# MotorController-ControlCard.net
KiCad netlist of a schematic drawn in EAGLE
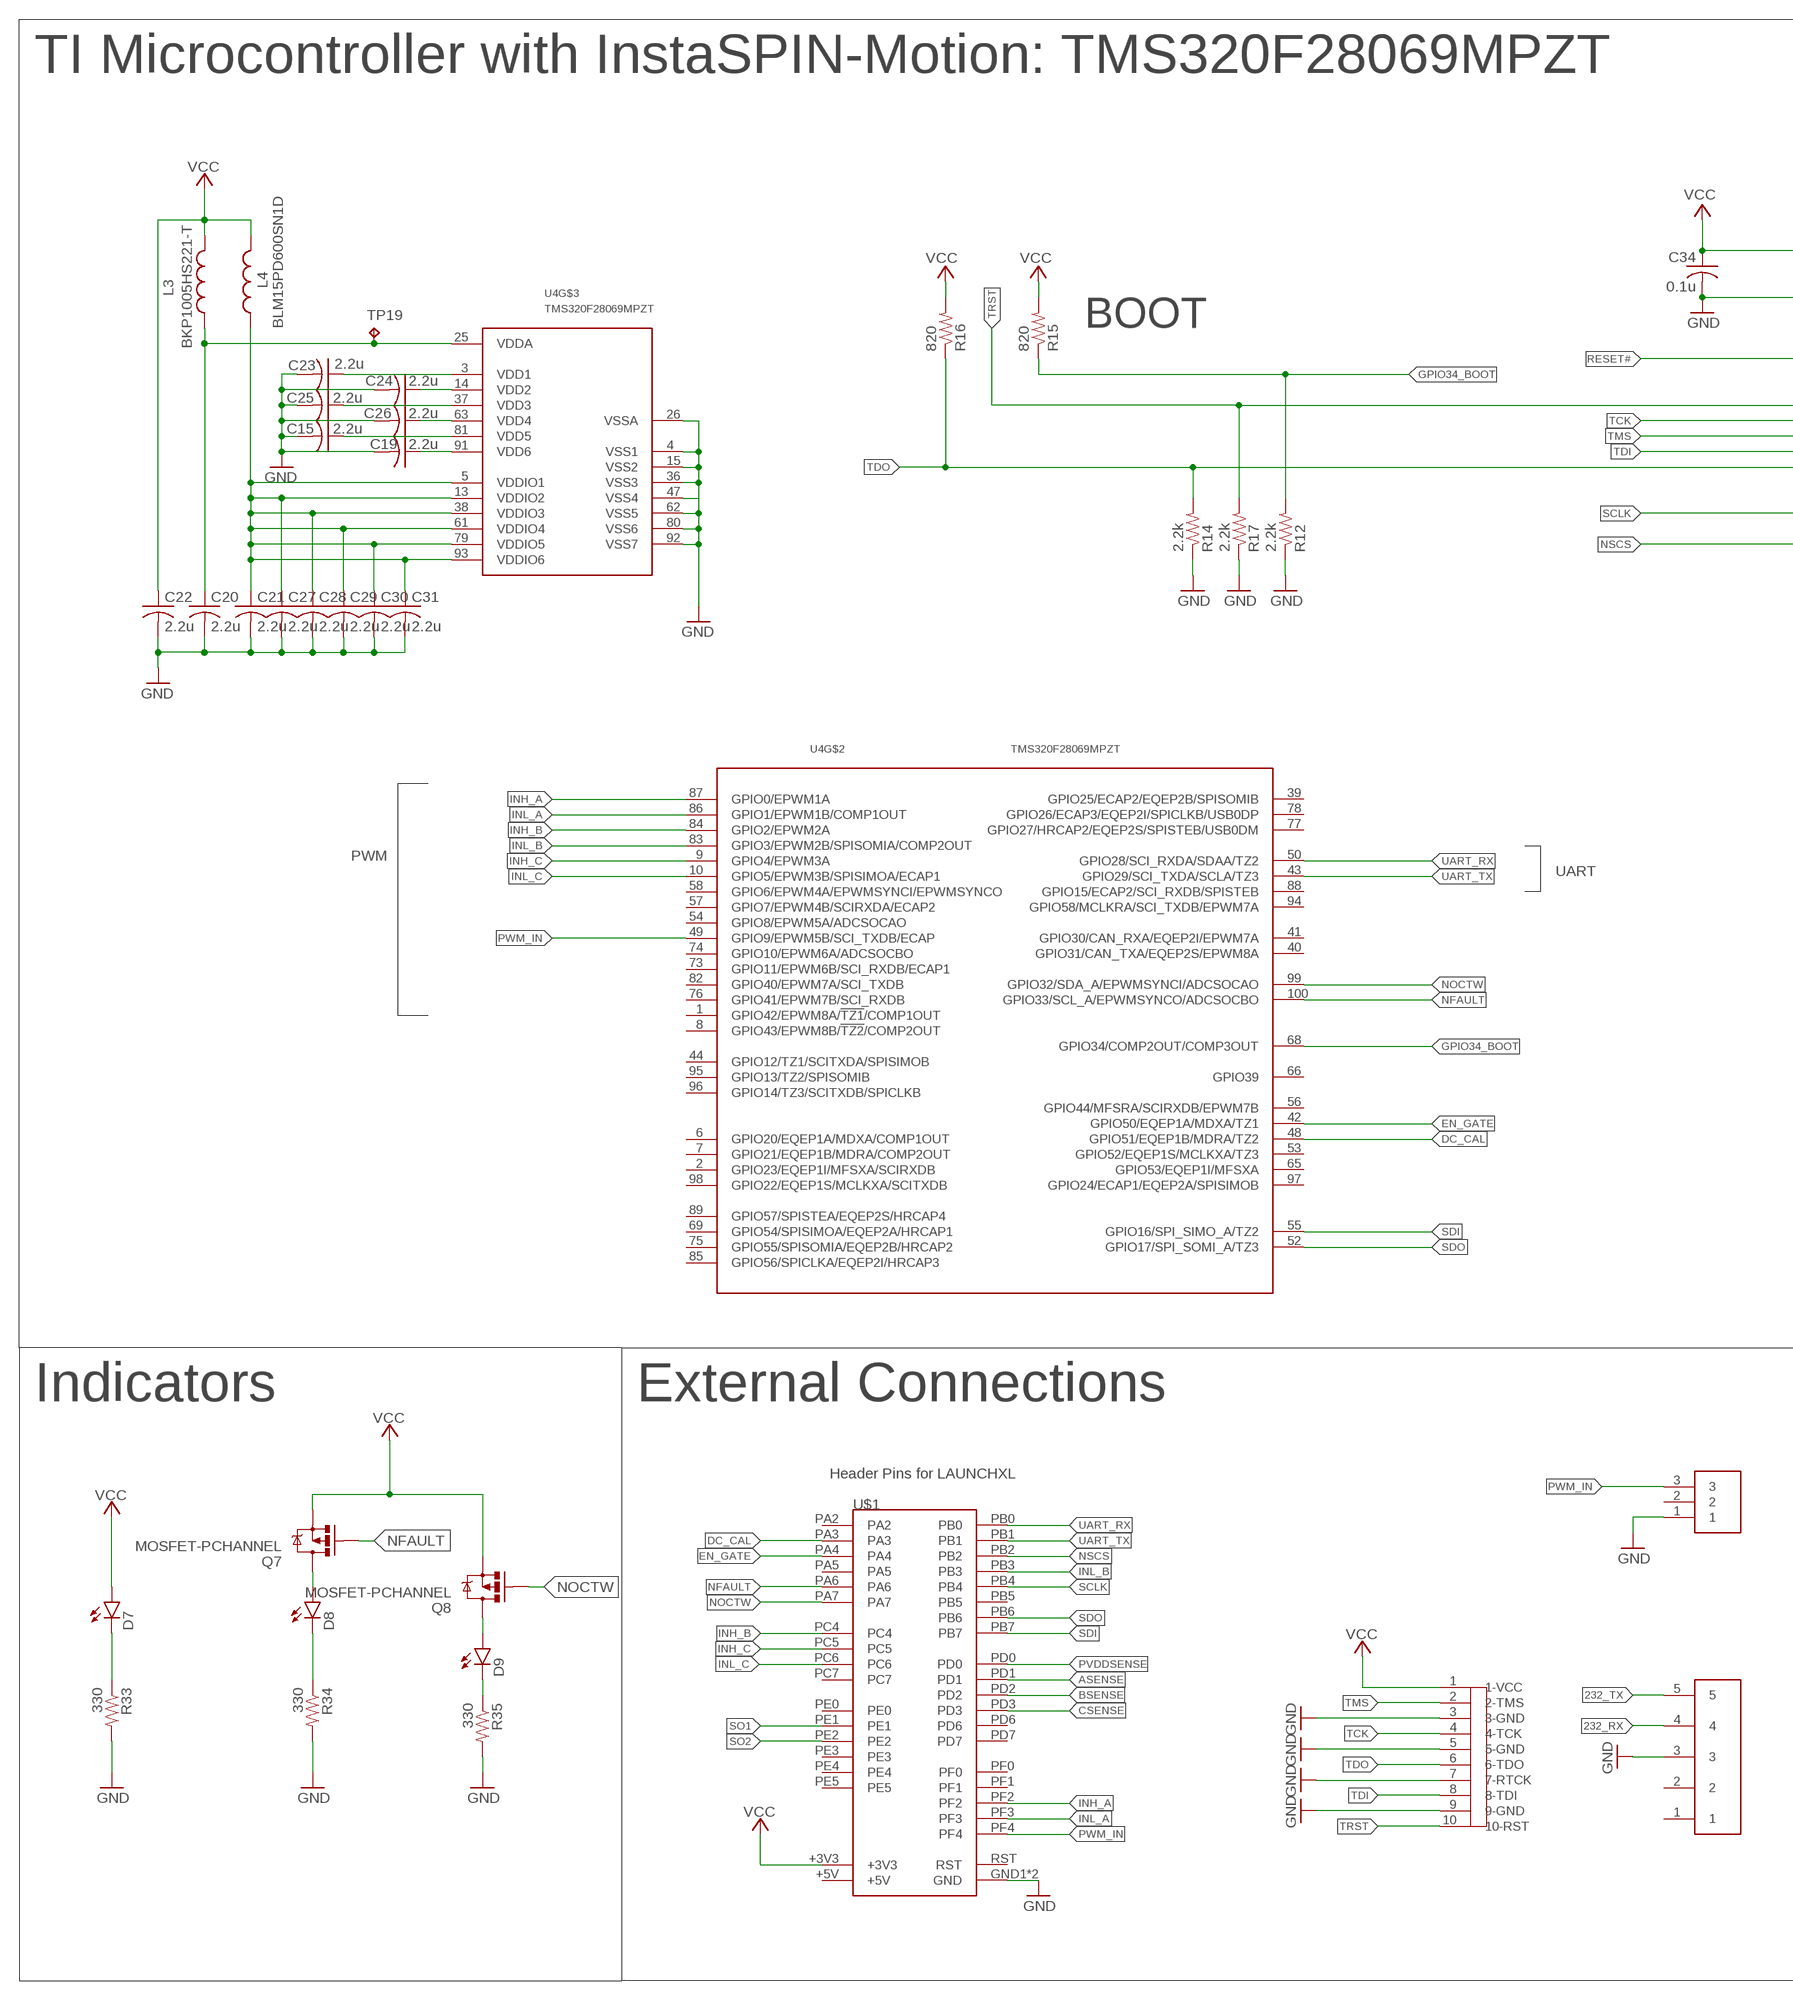
[diagram p0: schematic, sheet 1, part 1 of 2]
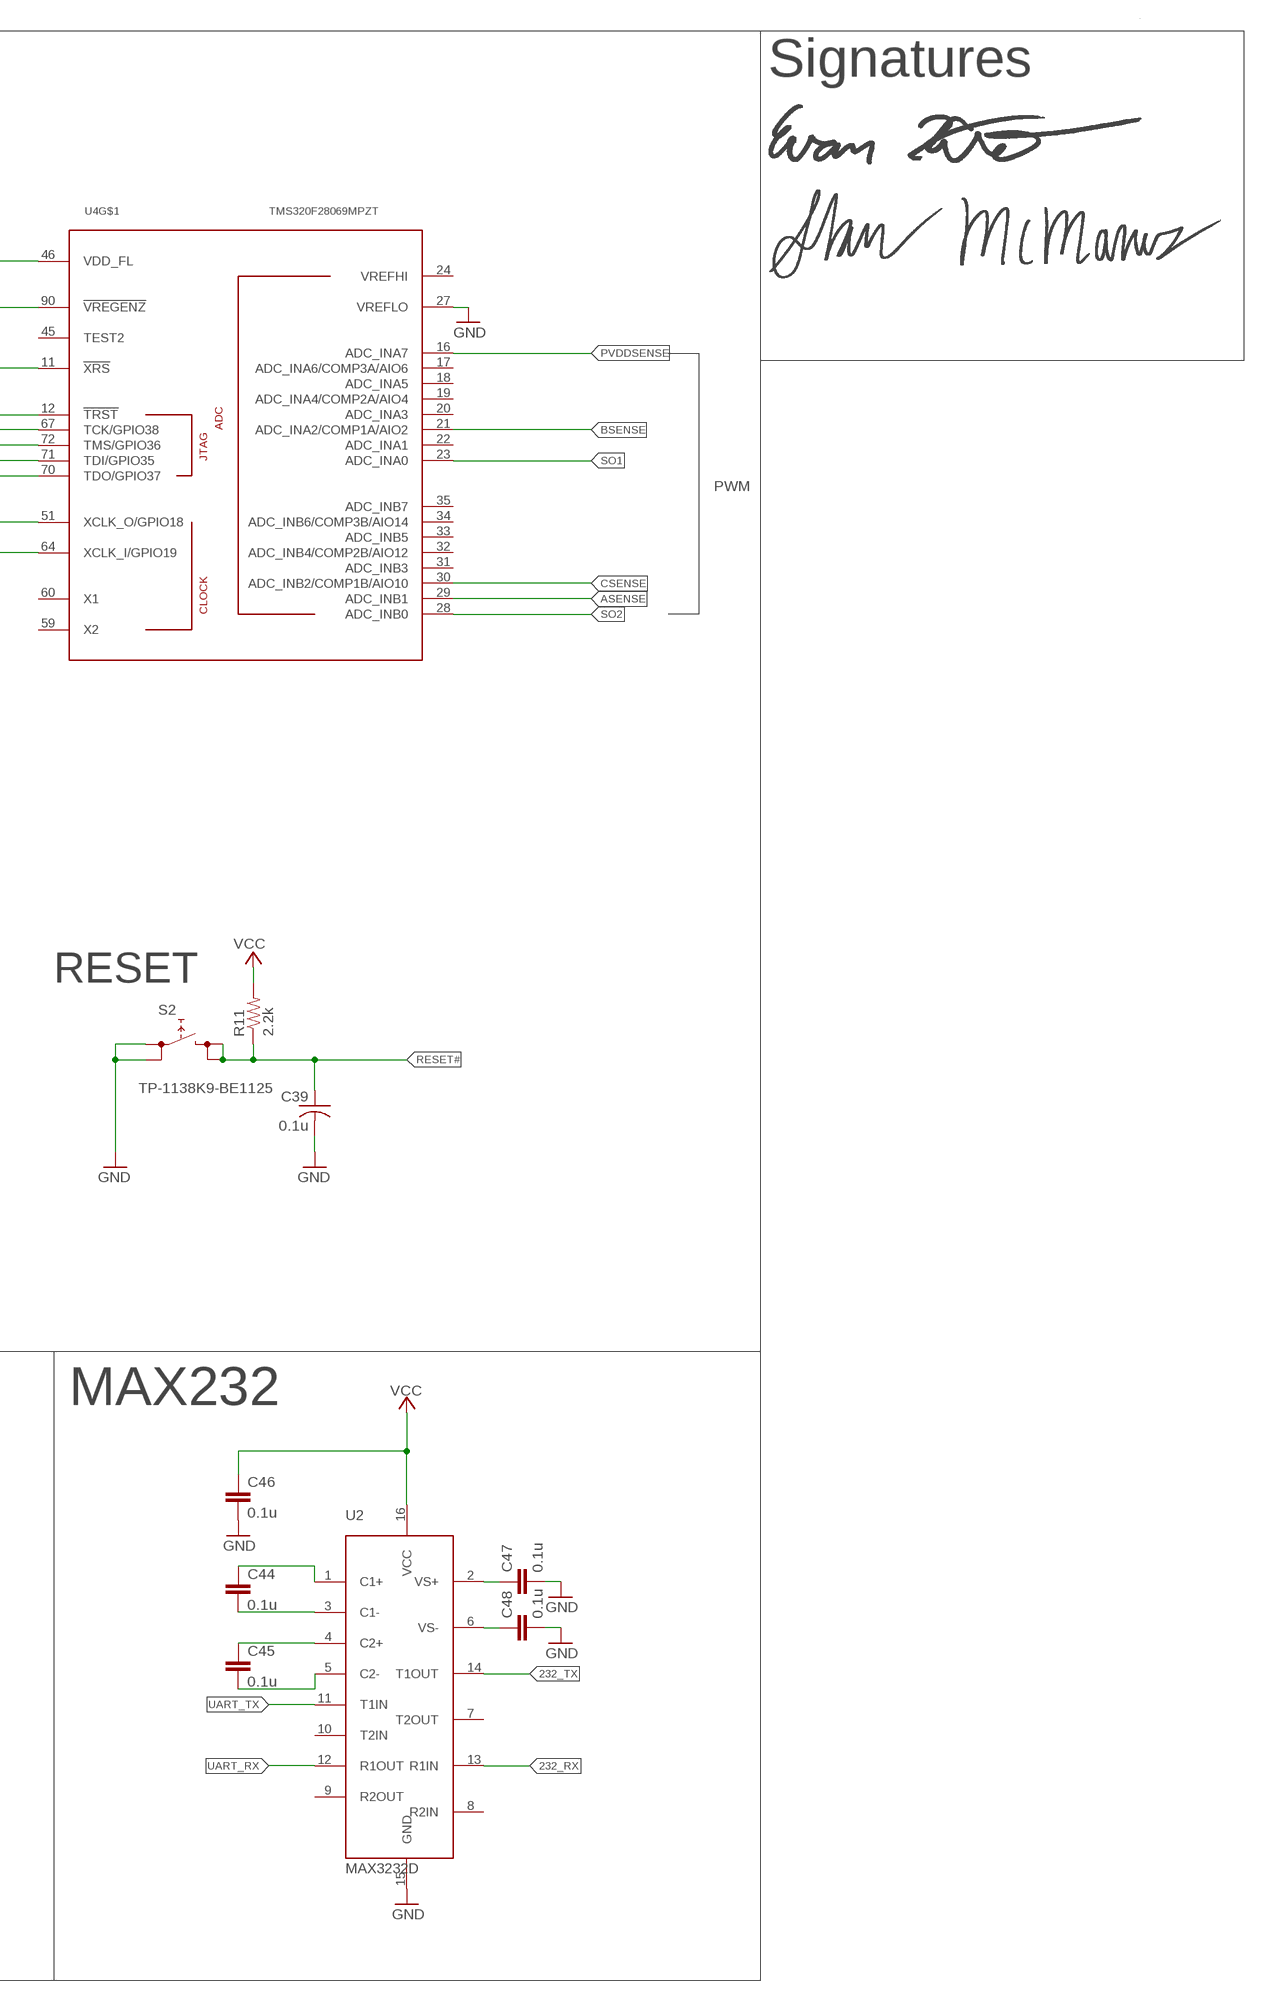
[diagram p1: schematic, sheet 1, part 2 of 2]

(export (version "E")
  (design (tool "Eeschema 10.0.6"))
  (components
    (comp (ref "C15")
      (value "2.2u")
      (footprint "eagle-import:C0402")
      (libsource (lib "eagle-import") (part "C-USC0402"))
    )
    (comp (ref "C19")
      (value "2.2u")
      (footprint "eagle-import:C0402")
      (libsource (lib "eagle-import") (part "C-USC0402"))
    )
    (comp (ref "C20")
      (value "2.2u")
      (footprint "eagle-import:C0402")
      (libsource (lib "eagle-import") (part "C-USC0402"))
    )
    (comp (ref "C21")
      (value "2.2u")
      (footprint "eagle-import:C0402")
      (libsource (lib "eagle-import") (part "C-USC0402"))
    )
    (comp (ref "C22")
      (value "2.2u")
      (footprint "eagle-import:C0402")
      (libsource (lib "eagle-import") (part "C-USC0402"))
    )
    (comp (ref "C23")
      (value "2.2u")
      (footprint "eagle-import:C0402")
      (libsource (lib "eagle-import") (part "C-USC0402"))
    )
    (comp (ref "C24")
      (value "2.2u")
      (footprint "eagle-import:C0402")
      (libsource (lib "eagle-import") (part "C-USC0402"))
    )
    (comp (ref "C25")
      (value "2.2u")
      (footprint "eagle-import:C0402")
      (libsource (lib "eagle-import") (part "C-USC0402"))
    )
    (comp (ref "C26")
      (value "2.2u")
      (footprint "eagle-import:C0402")
      (libsource (lib "eagle-import") (part "C-USC0402"))
    )
    (comp (ref "C27")
      (value "2.2u")
      (footprint "eagle-import:C0402")
      (libsource (lib "eagle-import") (part "C-USC0402"))
    )
    (comp (ref "C28")
      (value "2.2u")
      (footprint "eagle-import:C0402")
      (libsource (lib "eagle-import") (part "C-USC0402"))
    )
    (comp (ref "C29")
      (value "2.2u")
      (footprint "eagle-import:C0402")
      (libsource (lib "eagle-import") (part "C-USC0402"))
    )
    (comp (ref "C30")
      (value "2.2u")
      (footprint "eagle-import:C0402")
      (libsource (lib "eagle-import") (part "C-USC0402"))
    )
    (comp (ref "C31")
      (value "2.2u")
      (footprint "eagle-import:C0402")
      (libsource (lib "eagle-import") (part "C-USC0402"))
    )
    (comp (ref "C34")
      (value "0.1u")
      (footprint "eagle-import:C0402")
      (libsource (lib "eagle-import") (part "C-USC0402"))
    )
    (comp (ref "C39")
      (value "0.1u")
      (footprint "eagle-import:C0402")
      (libsource (lib "eagle-import") (part "C-USC0402"))
    )
    (comp (ref "C44")
      (value "0.1u")
      (footprint "eagle-import:0805")
      (libsource (lib "eagle-import") (part "CAP0805"))
    )
    (comp (ref "C45")
      (value "0.1u")
      (footprint "eagle-import:0805")
      (libsource (lib "eagle-import") (part "CAP0805"))
    )
    (comp (ref "C46")
      (value "0.1u")
      (footprint "eagle-import:0805")
      (libsource (lib "eagle-import") (part "CAP0805"))
    )
    (comp (ref "C47")
      (value "0.1u")
      (footprint "eagle-import:0805")
      (libsource (lib "eagle-import") (part "CAP0805"))
    )
    (comp (ref "C48")
      (value "0.1u")
      (footprint "eagle-import:0805")
      (libsource (lib "eagle-import") (part "CAP0805"))
    )
    (comp (ref "D7")
      (value "LED1206")
      (footprint "eagle-import:LED-1206")
      (libsource (lib "eagle-import") (part "LED1206"))
    )
    (comp (ref "D8")
      (value "LED1206")
      (footprint "eagle-import:LED-1206")
      (libsource (lib "eagle-import") (part "LED1206"))
    )
    (comp (ref "D9")
      (value "LED1206")
      (footprint "eagle-import:LED-1206")
      (libsource (lib "eagle-import") (part "LED1206"))
    )
    (comp (ref "J2")
      (value "SL03THROUGH_HOLE")
      (footprint "eagle-import:MOLEX_SL_03_TH")
      (fields (field (name "PARTNO") "0705550002"))
      (libsource (lib "eagle-import") (part "SL03THROUGH_HOLE"))
    )
    (comp (ref "L3")
      (value "BKP1005HS221-T")
      (footprint "eagle-import:R0402")
      (libsource (lib "eagle-import") (part "L-US0402"))
    )
    (comp (ref "L4")
      (value "BLM15PD600SN1D")
      (footprint "eagle-import:R0402")
      (libsource (lib "eagle-import") (part "L-US0402"))
    )
    (comp (ref "Q7")
      (value "MOSFET-PCHANNEL")
      (footprint "eagle-import:SOT23-3")
      (libsource (lib "eagle-import") (part "MOSFET-PCHANNEL"))
    )
    (comp (ref "Q8")
      (value "MOSFET-PCHANNEL")
      (footprint "eagle-import:SOT23-3")
      (libsource (lib "eagle-import") (part "MOSFET-PCHANNEL"))
    )
    (comp (ref "R11")
      (value "2.2k")
      (footprint "eagle-import:R0402")
      (libsource (lib "eagle-import") (part "R-US_R0402"))
    )
    (comp (ref "R12")
      (value "2.2k")
      (footprint "eagle-import:R0402")
      (libsource (lib "eagle-import") (part "R-US_R0402"))
    )
    (comp (ref "R14")
      (value "2.2k")
      (footprint "eagle-import:R0402")
      (libsource (lib "eagle-import") (part "R-US_R0402"))
    )
    (comp (ref "R15")
      (value "820")
      (footprint "eagle-import:R0402")
      (libsource (lib "eagle-import") (part "R-US_R0402"))
    )
    (comp (ref "R16")
      (value "820")
      (footprint "eagle-import:R0402")
      (libsource (lib "eagle-import") (part "R-US_R0402"))
    )
    (comp (ref "R17")
      (value "2.2k")
      (footprint "eagle-import:R0402")
      (libsource (lib "eagle-import") (part "R-US_R0402"))
    )
    (comp (ref "R33")
      (value "330")
      (footprint "eagle-import:0805")
      (libsource (lib "eagle-import") (part "RESISTOR0805-RES"))
    )
    (comp (ref "R34")
      (value "330")
      (footprint "eagle-import:0805")
      (libsource (lib "eagle-import") (part "RESISTOR0805-RES"))
    )
    (comp (ref "R35")
      (value "330")
      (footprint "eagle-import:0805")
      (libsource (lib "eagle-import") (part "RESISTOR0805-RES"))
    )
    (comp (ref "S2")
      (value "TP-1138K9-BE1125")
      (footprint "eagle-import:FSMJSMA")
      (libsource (lib "eagle-import") (part "FSMJSMA"))
    )
    (comp (ref "TP19")
      (value "TESTPAD_TPB1,27")
      (footprint "eagle-import:TESTPAD_B1,27")
      (libsource (lib "eagle-import") (part "TESTPAD_TPB1,27"))
    )
    (comp (ref "U$1")
      (value "TIVA-123")
      (footprint "eagle-import:TIVA-C")
      (libsource (lib "eagle-import") (part "TIVA-123"))
    )
    (comp (ref "U$2")
      (value "IDC_BOX_HEADER_2X5_1.27MM")
      (footprint "eagle-import:1.27MM_2X5_BOX_HEADER_STRAIGHT")
      (libsource (lib "eagle-import") (part "IDC_BOX_HEADER_2X5_1.27MM"))
    )
    (comp (ref "U$3")
      (value "EVAN_HITE_SIGNATURE")
      (footprint "eagle-import:EVAN_HITE_SIGNATURE")
      (libsource (lib "eagle-import") (part "EVAN_HITE_SIGNATURE"))
    )
    (comp (ref "U$4")
      (value "5PIN")
      (footprint "eagle-import:5PIN")
      (libsource (lib "eagle-import") (part "5PIN"))
    )
    (comp (ref "U$5")
      (value "SHAUN_MCMANUS_SIGNATURE")
      (footprint "eagle-import:SHAUN_MCMANUS_SIGNATURE")
      (libsource (lib "eagle-import") (part "SHAUN_MCMANUS_SIGNATURE"))
    )
    (comp (ref "U2")
      (value "MAX3232D")
      (footprint "eagle-import:SOIC16")
      (libsource (lib "eagle-import") (part "MAX232D3"))
    )
    (comp (ref "U4")
      (value "TMS320F28069MPZT")
      (footprint "eagle-import:PQFP100")
      (libsource (lib "eagle-import") (part "TMS320F28069PZSR"))
    )
  )
  (nets
    (net (code "1") (name "/+5V") (class "Default")
      (node (ref "U$1") (pin "+5V") (pinfunction "+5V_+5V") (pintype "power_in"))
    )
    (net (code "2") (name "/RST") (class "Default")
      (node (ref "U$1") (pin "RST") (pinfunction "RST_RST") (pintype "power_in"))
    )
    (net (code "3") (name "232_RX") (class "Default")
      (node (ref "U$4") (pin "4") (pinfunction "4_4") (pintype "bidirectional"))
      (node (ref "U2") (pin "13") (pinfunction "R1IN_13") (pintype "bidirectional"))
    )
    (net (code "4") (name "232_TX") (class "Default")
      (node (ref "U$4") (pin "5") (pinfunction "5_5") (pintype "bidirectional"))
      (node (ref "U2") (pin "14") (pinfunction "T1OUT_14") (pintype "bidirectional"))
    )
    (net (code "5") (name "ASENSE") (class "Default")
      (node (ref "U$1") (pin "PD1") (pinfunction "PD1_PD1") (pintype "bidirectional"))
      (node (ref "U4") (pin "29") (pinfunction "ADC_INB1_29") (pintype "input"))
    )
    (net (code "6") (name "BSENSE") (class "Default")
      (node (ref "U$1") (pin "PD2") (pinfunction "PD2_PD2") (pintype "bidirectional"))
      (node (ref "U4") (pin "21") (pinfunction "ADC_INA2/COMP1A/AIO2_21") (pintype "bidirectional"))
    )
    (net (code "7") (name "CSENSE") (class "Default")
      (node (ref "U$1") (pin "PD3") (pinfunction "PD3_PD3") (pintype "bidirectional"))
      (node (ref "U4") (pin "30") (pinfunction "ADC_INB2/COMP1B/AIO10_30") (pintype "bidirectional"))
    )
    (net (code "8") (name "DC_CAL") (class "Default")
      (node (ref "U$1") (pin "PA3") (pinfunction "PA3_PA3") (pintype "bidirectional"))
      (node (ref "U4") (pin "48") (pinfunction "GPIO51/EQEP1B/MDRA/TZ2_48") (pintype "bidirectional"))
    )
    (net (code "9") (name "EN_GATE") (class "Default")
      (node (ref "U$1") (pin "PA4") (pinfunction "PA4_PA4") (pintype "bidirectional"))
      (node (ref "U4") (pin "42") (pinfunction "GPIO50/EQEP1A/MDXA/TZ1_42") (pintype "bidirectional"))
    )
    (net (code "10") (name "GND") (class "Default")
      (node (ref "C15") (pin "2") (pinfunction "2_2") (pintype "passive"))
      (node (ref "C19") (pin "2") (pinfunction "2_2") (pintype "passive"))
      (node (ref "C20") (pin "2") (pinfunction "2_2") (pintype "passive"))
      (node (ref "C21") (pin "2") (pinfunction "2_2") (pintype "passive"))
      (node (ref "C22") (pin "2") (pinfunction "2_2") (pintype "passive"))
      (node (ref "C23") (pin "2") (pinfunction "2_2") (pintype "passive"))
      (node (ref "C24") (pin "2") (pinfunction "2_2") (pintype "passive"))
      (node (ref "C25") (pin "2") (pinfunction "2_2") (pintype "passive"))
      (node (ref "C26") (pin "2") (pinfunction "2_2") (pintype "passive"))
      (node (ref "C27") (pin "2") (pinfunction "2_2") (pintype "passive"))
      (node (ref "C28") (pin "2") (pinfunction "2_2") (pintype "passive"))
      (node (ref "C29") (pin "2") (pinfunction "2_2") (pintype "passive"))
      (node (ref "C30") (pin "2") (pinfunction "2_2") (pintype "passive"))
      (node (ref "C31") (pin "2") (pinfunction "2_2") (pintype "passive"))
      (node (ref "C34") (pin "2") (pinfunction "2_2") (pintype "passive"))
      (node (ref "C39") (pin "2") (pinfunction "2_2") (pintype "passive"))
      (node (ref "C46") (pin "2") (pinfunction "2_2") (pintype "passive"))
      (node (ref "C47") (pin "2") (pinfunction "2_2") (pintype "passive"))
      (node (ref "C48") (pin "2") (pinfunction "2_2") (pintype "passive"))
      (node (ref "J2") (pin "1") (pinfunction "1_1") (pintype "bidirectional"))
      (node (ref "R12") (pin "1") (pinfunction "1_1") (pintype "passive"))
      (node (ref "R14") (pin "1") (pinfunction "1_1") (pintype "passive"))
      (node (ref "R17") (pin "1") (pinfunction "1_1") (pintype "passive"))
      (node (ref "R33") (pin "2") (pinfunction "2_2") (pintype "passive"))
      (node (ref "R34") (pin "2") (pinfunction "2_2") (pintype "passive"))
      (node (ref "R35") (pin "2") (pinfunction "2_2") (pintype "passive"))
      (node (ref "S2") (pin "P$1") (pinfunction "0_P$1") (pintype "passive"))
      (node (ref "S2") (pin "P$2") (pinfunction "0_P$2") (pintype "passive"))
      (node (ref "U$1") (pin "GND1") (pinfunction "GND_GND1") (pintype "power_in"))
      (node (ref "U$1") (pin "GND2") (pinfunction "GND_GND2") (pintype "power_in"))
      (node (ref "U$2") (pin "3") (pinfunction "3-GND_3") (pintype "bidirectional"))
      (node (ref "U$2") (pin "5") (pinfunction "5-GND_5") (pintype "bidirectional"))
      (node (ref "U$2") (pin "7") (pinfunction "7-RTCK_7") (pintype "bidirectional"))
      (node (ref "U$2") (pin "9") (pinfunction "9-GND_9") (pintype "bidirectional"))
      (node (ref "U$4") (pin "3") (pinfunction "3_3") (pintype "bidirectional"))
      (node (ref "U2") (pin "15") (pinfunction "GND_15") (pintype "bidirectional"))
      (node (ref "U4") (pin "15") (pinfunction "VSS2_15") (pintype "power_in"))
      (node (ref "U4") (pin "26") (pinfunction "VSSA_26") (pintype "power_in"))
      (node (ref "U4") (pin "27") (pinfunction "VREFLO_27") (pintype "input"))
      (node (ref "U4") (pin "36") (pinfunction "VSS3_36") (pintype "power_in"))
      (node (ref "U4") (pin "4") (pinfunction "VSS1_4") (pintype "power_in"))
      (node (ref "U4") (pin "47") (pinfunction "VSS4_47") (pintype "power_in"))
      (node (ref "U4") (pin "62") (pinfunction "VSS5_62") (pintype "power_in"))
      (node (ref "U4") (pin "80") (pinfunction "VSS6_80") (pintype "power_in"))
      (node (ref "U4") (pin "90") (pinfunction "~{VREGENZ}_90") (pintype "input"))
      (node (ref "U4") (pin "92") (pinfunction "VSS7_92") (pintype "power_in"))
    )
    (net (code "11") (name "GPIO34_BOOT") (class "Default")
      (node (ref "R12") (pin "2") (pinfunction "2_2") (pintype "passive"))
      (node (ref "R15") (pin "1") (pinfunction "1_1") (pintype "passive"))
      (node (ref "U4") (pin "68") (pinfunction "GPIO34/COMP2OUT/COMP3OUT_68") (pintype "bidirectional"))
    )
    (net (code "12") (name "INH_A") (class "Default")
      (node (ref "U$1") (pin "PF2") (pinfunction "PF2_PF2") (pintype "bidirectional"))
      (node (ref "U4") (pin "87") (pinfunction "GPIO0/EPWM1A_87") (pintype "bidirectional"))
    )
    (net (code "13") (name "INH_B") (class "Default")
      (node (ref "U$1") (pin "PC4") (pinfunction "PC4_PC4") (pintype "bidirectional"))
      (node (ref "U4") (pin "84") (pinfunction "GPIO2/EPWM2A_84") (pintype "bidirectional"))
    )
    (net (code "14") (name "INH_C") (class "Default")
      (node (ref "U$1") (pin "PC5") (pinfunction "PC5_PC5") (pintype "bidirectional"))
      (node (ref "U4") (pin "9") (pinfunction "GPIO4/EPWM3A_9") (pintype "bidirectional"))
    )
    (net (code "15") (name "INL_A") (class "Default")
      (node (ref "U$1") (pin "PF3") (pinfunction "PF3_PF3") (pintype "bidirectional"))
      (node (ref "U4") (pin "86") (pinfunction "GPIO1/EPWM1B/COMP1OUT_86") (pintype "bidirectional"))
    )
    (net (code "16") (name "INL_B") (class "Default")
      (node (ref "U$1") (pin "PB3") (pinfunction "PB3_PB3") (pintype "bidirectional"))
      (node (ref "U4") (pin "83") (pinfunction "GPIO3/EPWM2B/SPISOMIA/COMP2OUT_83") (pintype "bidirectional"))
    )
    (net (code "17") (name "INL_C") (class "Default")
      (node (ref "U$1") (pin "PC6") (pinfunction "PC6_PC6") (pintype "bidirectional"))
      (node (ref "U4") (pin "10") (pinfunction "GPIO5/EPWM3B/SPISIMOA/ECAP1_10") (pintype "bidirectional"))
    )
    (net (code "18") (name "NFAULT") (class "Default")
      (node (ref "Q7") (pin "1") (pinfunction "G_1") (pintype "passive"))
      (node (ref "U$1") (pin "PA6") (pinfunction "PA6_PA6") (pintype "bidirectional"))
      (node (ref "U4") (pin "100") (pinfunction "GPIO33/SCL_A/EPWMSYNCO/ADCSOCBO_100") (pintype "bidirectional"))
    )
    (net (code "19") (name "NOCTW") (class "Default")
      (node (ref "Q8") (pin "1") (pinfunction "G_1") (pintype "passive"))
      (node (ref "U$1") (pin "PA7") (pinfunction "PA7_PA7") (pintype "bidirectional"))
      (node (ref "U4") (pin "99") (pinfunction "GPIO32/SDA_A/EPWMSYNCI/ADCSOCAO_99") (pintype "bidirectional"))
    )
    (net (code "20") (name "NSCS") (class "Default")
      (node (ref "U$1") (pin "PB2") (pinfunction "PB2_PB2") (pintype "bidirectional"))
      (node (ref "U4") (pin "64") (pinfunction "XCLK_I/GPIO19_64") (pintype "input"))
    )
    (net (code "21") (name "Net-(D7-PadC)") (class "Default")
      (node (ref "D7") (pin "C") (pinfunction "C_C") (pintype "passive"))
      (node (ref "R33") (pin "1") (pinfunction "1_1") (pintype "passive"))
    )
    (net (code "22") (name "Net-(D8-PadC)") (class "Default")
      (node (ref "D8") (pin "C") (pinfunction "C_C") (pintype "passive"))
      (node (ref "R34") (pin "1") (pinfunction "1_1") (pintype "passive"))
    )
    (net (code "23") (name "Net-(D9-PadC)") (class "Default")
      (node (ref "D9") (pin "C") (pinfunction "C_C") (pintype "passive"))
      (node (ref "R35") (pin "1") (pinfunction "1_1") (pintype "passive"))
    )
    (net (code "24") (name "Net-(Q7-D)") (class "Default")
      (node (ref "D8") (pin "A") (pinfunction "A_A") (pintype "passive"))
      (node (ref "Q7") (pin "3") (pinfunction "D_3") (pintype "passive"))
    )
    (net (code "25") (name "Net-(Q8-D)") (class "Default")
      (node (ref "D9") (pin "A") (pinfunction "A_A") (pintype "passive"))
      (node (ref "Q8") (pin "3") (pinfunction "D_3") (pintype "passive"))
    )
    (net (code "26") (name "Net-(U2-C1+)") (class "Default")
      (node (ref "C44") (pin "1") (pinfunction "1_1") (pintype "passive"))
      (node (ref "U2") (pin "1") (pinfunction "C1+_1") (pintype "bidirectional"))
    )
    (net (code "27") (name "Net-(U2-C1-)") (class "Default")
      (node (ref "C44") (pin "2") (pinfunction "2_2") (pintype "passive"))
      (node (ref "U2") (pin "3") (pinfunction "C1-_3") (pintype "bidirectional"))
    )
    (net (code "28") (name "Net-(U2-C2+)") (class "Default")
      (node (ref "C45") (pin "1") (pinfunction "1_1") (pintype "passive"))
      (node (ref "U2") (pin "4") (pinfunction "C2+_4") (pintype "bidirectional"))
    )
    (net (code "29") (name "Net-(U2-C2-)") (class "Default")
      (node (ref "C45") (pin "2") (pinfunction "2_2") (pintype "passive"))
      (node (ref "U2") (pin "5") (pinfunction "C2-_5") (pintype "bidirectional"))
    )
    (net (code "30") (name "Net-(U2-VS+)") (class "Default")
      (node (ref "C47") (pin "1") (pinfunction "1_1") (pintype "passive"))
      (node (ref "U2") (pin "2") (pinfunction "VS+_2") (pintype "bidirectional"))
    )
    (net (code "31") (name "Net-(U2-VS-)") (class "Default")
      (node (ref "C48") (pin "1") (pinfunction "1_1") (pintype "passive"))
      (node (ref "U2") (pin "6") (pinfunction "VS-_6") (pintype "bidirectional"))
    )
    (net (code "32") (name "Net-(U4C-VDD1)") (class "Default")
      (node (ref "C23") (pin "1") (pinfunction "1_1") (pintype "passive"))
      (node (ref "U4") (pin "3") (pinfunction "VDD1_3") (pintype "power_in"))
    )
    (net (code "33") (name "Net-(U4C-VDD2)") (class "Default")
      (node (ref "C24") (pin "1") (pinfunction "1_1") (pintype "passive"))
      (node (ref "U4") (pin "14") (pinfunction "VDD2_14") (pintype "power_in"))
    )
    (net (code "34") (name "Net-(U4C-VDD3)") (class "Default")
      (node (ref "C25") (pin "1") (pinfunction "1_1") (pintype "passive"))
      (node (ref "U4") (pin "37") (pinfunction "VDD3_37") (pintype "power_in"))
    )
    (net (code "35") (name "Net-(U4C-VDD4)") (class "Default")
      (node (ref "C26") (pin "1") (pinfunction "1_1") (pintype "passive"))
      (node (ref "U4") (pin "63") (pinfunction "VDD4_63") (pintype "power_in"))
    )
    (net (code "36") (name "Net-(U4C-VDD5)") (class "Default")
      (node (ref "C15") (pin "1") (pinfunction "1_1") (pintype "passive"))
      (node (ref "U4") (pin "81") (pinfunction "VDD5_81") (pintype "power_in"))
    )
    (net (code "37") (name "Net-(U4C-VDD6)") (class "Default")
      (node (ref "C19") (pin "1") (pinfunction "1_1") (pintype "passive"))
      (node (ref "U4") (pin "91") (pinfunction "VDD6_91") (pintype "power_in"))
    )
    (net (code "38") (name "Net-(U4C-VDDA)") (class "Default")
      (node (ref "C20") (pin "1") (pinfunction "1_1") (pintype "passive"))
      (node (ref "L3") (pin "1") (pinfunction "1_1") (pintype "passive"))
      (node (ref "TP19") (pin "TP") (pinfunction "TP_TP") (pintype "input"))
      (node (ref "U4") (pin "25") (pinfunction "VDDA_25") (pintype "power_in"))
    )
    (net (code "39") (name "Net-(U4C-VDDIO1)") (class "Default")
      (node (ref "C21") (pin "1") (pinfunction "1_1") (pintype "passive"))
      (node (ref "C27") (pin "1") (pinfunction "1_1") (pintype "passive"))
      (node (ref "C28") (pin "1") (pinfunction "1_1") (pintype "passive"))
      (node (ref "C29") (pin "1") (pinfunction "1_1") (pintype "passive"))
      (node (ref "C30") (pin "1") (pinfunction "1_1") (pintype "passive"))
      (node (ref "C31") (pin "1") (pinfunction "1_1") (pintype "passive"))
      (node (ref "L4") (pin "1") (pinfunction "1_1") (pintype "passive"))
      (node (ref "U4") (pin "13") (pinfunction "VDDIO2_13") (pintype "power_in"))
      (node (ref "U4") (pin "38") (pinfunction "VDDIO3_38") (pintype "power_in"))
      (node (ref "U4") (pin "5") (pinfunction "VDDIO1_5") (pintype "power_in"))
      (node (ref "U4") (pin "61") (pinfunction "VDDIO4_61") (pintype "power_in"))
      (node (ref "U4") (pin "79") (pinfunction "VDDIO5_79") (pintype "power_in"))
      (node (ref "U4") (pin "93") (pinfunction "VDDIO6_93") (pintype "power_in"))
    )
    (net (code "40") (name "PVDDSENSE") (class "Default")
      (node (ref "U$1") (pin "PD0") (pinfunction "PD0_PD0") (pintype "bidirectional"))
      (node (ref "U4") (pin "16") (pinfunction "ADC_INA7_16") (pintype "input"))
    )
    (net (code "41") (name "PWM_IN") (class "Default")
      (node (ref "J2") (pin "3") (pinfunction "3_3") (pintype "bidirectional"))
      (node (ref "U$1") (pin "PF4") (pinfunction "PF4_PF4") (pintype "bidirectional"))
      (node (ref "U4") (pin "49") (pinfunction "GPIO9/EPWM5B/SCI_TXDB/ECAP_49") (pintype "bidirectional"))
    )
    (net (code "42") (name "RESET#") (class "Default")
      (node (ref "C39") (pin "1") (pinfunction "1_1") (pintype "passive"))
      (node (ref "R11") (pin "1") (pinfunction "1_1") (pintype "passive"))
      (node (ref "S2") (pin "P$3") (pinfunction "1_P$3") (pintype "passive"))
      (node (ref "S2") (pin "P$4") (pinfunction "1_P$4") (pintype "passive"))
      (node (ref "U4") (pin "11") (pinfunction "~{XRS}_11") (pintype "bidirectional"))
    )
    (net (code "43") (name "SCLK") (class "Default")
      (node (ref "U$1") (pin "PB4") (pinfunction "PB4_PB4") (pintype "bidirectional"))
      (node (ref "U4") (pin "51") (pinfunction "XCLK_O/GPIO18_51") (pintype "output"))
    )
    (net (code "44") (name "SDI") (class "Default")
      (node (ref "U$1") (pin "PB7") (pinfunction "PB7_PB7") (pintype "bidirectional"))
      (node (ref "U4") (pin "55") (pinfunction "GPIO16/SPI_SIMO_A/TZ2_55") (pintype "bidirectional"))
    )
    (net (code "45") (name "SDO") (class "Default")
      (node (ref "U$1") (pin "PB6") (pinfunction "PB6_PB6") (pintype "bidirectional"))
      (node (ref "U4") (pin "52") (pinfunction "GPIO17/SPI_SOMI_A/TZ3_52") (pintype "bidirectional"))
    )
    (net (code "46") (name "SO1") (class "Default")
      (node (ref "U$1") (pin "PE1") (pinfunction "PE1_PE1") (pintype "bidirectional"))
      (node (ref "U4") (pin "23") (pinfunction "ADC_INA0_23") (pintype "input"))
    )
    (net (code "47") (name "SO2") (class "Default")
      (node (ref "U$1") (pin "PE2") (pinfunction "PE2_PE2") (pintype "bidirectional"))
      (node (ref "U4") (pin "28") (pinfunction "ADC_INB0_28") (pintype "input"))
    )
    (net (code "48") (name "TCK") (class "Default")
      (node (ref "U$2") (pin "4") (pinfunction "4-TCK_4") (pintype "bidirectional"))
      (node (ref "U4") (pin "67") (pinfunction "TCK/GPIO38_67") (pintype "input"))
    )
    (net (code "49") (name "TDI") (class "Default")
      (node (ref "U$2") (pin "8") (pinfunction "8-TDI_8") (pintype "bidirectional"))
      (node (ref "U4") (pin "71") (pinfunction "TDI/GPIO35_71") (pintype "input"))
    )
    (net (code "50") (name "TDO") (class "Default")
      (node (ref "R14") (pin "2") (pinfunction "2_2") (pintype "passive"))
      (node (ref "R16") (pin "1") (pinfunction "1_1") (pintype "passive"))
      (node (ref "U$2") (pin "6") (pinfunction "6-TDO_6") (pintype "bidirectional"))
      (node (ref "U4") (pin "70") (pinfunction "TDO/GPIO37_70") (pintype "output"))
    )
    (net (code "51") (name "TMS") (class "Default")
      (node (ref "U$2") (pin "2") (pinfunction "2-TMS_2") (pintype "bidirectional"))
      (node (ref "U4") (pin "72") (pinfunction "TMS/GPIO36_72") (pintype "input"))
    )
    (net (code "52") (name "TRST") (class "Default")
      (node (ref "R17") (pin "2") (pinfunction "2_2") (pintype "passive"))
      (node (ref "U$2") (pin "10") (pinfunction "10-RST_10") (pintype "bidirectional"))
      (node (ref "U4") (pin "12") (pinfunction "~{TRST}_12") (pintype "input"))
    )
    (net (code "53") (name "UART_RX") (class "Default")
      (node (ref "U$1") (pin "PB0") (pinfunction "PB0_PB0") (pintype "bidirectional"))
      (node (ref "U2") (pin "12") (pinfunction "R1OUT_12") (pintype "bidirectional"))
      (node (ref "U4") (pin "50") (pinfunction "GPIO28/SCI_RXDA/SDAA/TZ2_50") (pintype "bidirectional"))
    )
    (net (code "54") (name "UART_TX") (class "Default")
      (node (ref "U$1") (pin "PB1") (pinfunction "PB1_PB1") (pintype "bidirectional"))
      (node (ref "U2") (pin "11") (pinfunction "T1IN_11") (pintype "bidirectional"))
      (node (ref "U4") (pin "43") (pinfunction "GPIO29/SCI_TXDA/SCLA/TZ3_43") (pintype "bidirectional"))
    )
    (net (code "55") (name "VCC") (class "Default")
      (node (ref "C22") (pin "1") (pinfunction "1_1") (pintype "passive"))
      (node (ref "C34") (pin "1") (pinfunction "1_1") (pintype "passive"))
      (node (ref "C46") (pin "1") (pinfunction "1_1") (pintype "passive"))
      (node (ref "D7") (pin "A") (pinfunction "A_A") (pintype "passive"))
      (node (ref "L3") (pin "2") (pinfunction "2_2") (pintype "passive"))
      (node (ref "L4") (pin "2") (pinfunction "2_2") (pintype "passive"))
      (node (ref "Q7") (pin "2") (pinfunction "S_2") (pintype "passive"))
      (node (ref "Q8") (pin "2") (pinfunction "S_2") (pintype "passive"))
      (node (ref "R11") (pin "2") (pinfunction "2_2") (pintype "passive"))
      (node (ref "R15") (pin "2") (pinfunction "2_2") (pintype "passive"))
      (node (ref "R16") (pin "2") (pinfunction "2_2") (pintype "passive"))
      (node (ref "U$1") (pin "+3V3") (pinfunction "+3V3_+3V3") (pintype "power_in"))
      (node (ref "U$2") (pin "1") (pinfunction "1-VCC_1") (pintype "bidirectional"))
      (node (ref "U2") (pin "16") (pinfunction "VCC_16") (pintype "bidirectional"))
      (node (ref "U4") (pin "46") (pinfunction "VDD_FL_46") (pintype "power_in"))
    )
    (net (code "56") (name "unconnected-(J2-Pad2)") (class "Default")
      (node (ref "J2") (pin "2") (pinfunction "2_2") (pintype "bidirectional"))
    )
    (net (code "57") (name "unconnected-(U$1-PadPA2)") (class "Default")
      (node (ref "U$1") (pin "PA2") (pinfunction "PA2_PA2") (pintype "bidirectional"))
    )
    (net (code "58") (name "unconnected-(U$1-PadPA5)") (class "Default")
      (node (ref "U$1") (pin "PA5") (pinfunction "PA5_PA5") (pintype "bidirectional"))
    )
    (net (code "59") (name "unconnected-(U$1-PadPB5)") (class "Default")
      (node (ref "U$1") (pin "PB5") (pinfunction "PB5_PB5") (pintype "bidirectional"))
    )
    (net (code "60") (name "unconnected-(U$1-PadPC7)") (class "Default")
      (node (ref "U$1") (pin "PC7") (pinfunction "PC7_PC7") (pintype "bidirectional"))
    )
    (net (code "61") (name "unconnected-(U$1-PadPD6)") (class "Default")
      (node (ref "U$1") (pin "PD6") (pinfunction "PD6_PD6") (pintype "bidirectional"))
    )
    (net (code "62") (name "unconnected-(U$1-PadPD7)") (class "Default")
      (node (ref "U$1") (pin "PD7") (pinfunction "PD7_PD7") (pintype "bidirectional"))
    )
    (net (code "63") (name "unconnected-(U$1-PadPE0)") (class "Default")
      (node (ref "U$1") (pin "PE0") (pinfunction "PE0_PE0") (pintype "bidirectional"))
    )
    (net (code "64") (name "unconnected-(U$1-PadPE3)") (class "Default")
      (node (ref "U$1") (pin "PE3") (pinfunction "PE3_PE3") (pintype "bidirectional"))
    )
    (net (code "65") (name "unconnected-(U$1-PadPE4)") (class "Default")
      (node (ref "U$1") (pin "PE4") (pinfunction "PE4_PE4") (pintype "bidirectional"))
    )
    (net (code "66") (name "unconnected-(U$1-PadPE5)") (class "Default")
      (node (ref "U$1") (pin "PE5") (pinfunction "PE5_PE5") (pintype "bidirectional"))
    )
    (net (code "67") (name "unconnected-(U$1-PadPF0)") (class "Default")
      (node (ref "U$1") (pin "PF0") (pinfunction "PF0_PF0") (pintype "bidirectional"))
    )
    (net (code "68") (name "unconnected-(U$1-PadPF1)") (class "Default")
      (node (ref "U$1") (pin "PF1") (pinfunction "PF1_PF1") (pintype "bidirectional"))
    )
    (net (code "69") (name "unconnected-(U$4-Pad1)") (class "Default")
      (node (ref "U$4") (pin "1") (pinfunction "1_1") (pintype "bidirectional"))
    )
    (net (code "70") (name "unconnected-(U$4-Pad2)") (class "Default")
      (node (ref "U$4") (pin "2") (pinfunction "2_2") (pintype "bidirectional"))
    )
    (net (code "71") (name "unconnected-(U2-R2IN-Pad8)") (class "Default")
      (node (ref "U2") (pin "8") (pinfunction "R2IN_8") (pintype "bidirectional"))
    )
    (net (code "72") (name "unconnected-(U2-R2OUT-Pad9)") (class "Default")
      (node (ref "U2") (pin "9") (pinfunction "R2OUT_9") (pintype "bidirectional"))
    )
    (net (code "73") (name "unconnected-(U2-T2IN-Pad10)") (class "Default")
      (node (ref "U2") (pin "10") (pinfunction "T2IN_10") (pintype "bidirectional"))
    )
    (net (code "74") (name "unconnected-(U2-T2OUT-Pad7)") (class "Default")
      (node (ref "U2") (pin "7") (pinfunction "T2OUT_7") (pintype "bidirectional"))
    )
    (net (code "75") (name "unconnected-(U4A-ADC_INA1-Pad22)") (class "Default")
      (node (ref "U4") (pin "22") (pinfunction "ADC_INA1_22") (pintype "input"))
    )
    (net (code "76") (name "unconnected-(U4A-ADC_INA3-Pad20)") (class "Default")
      (node (ref "U4") (pin "20") (pinfunction "ADC_INA3_20") (pintype "input"))
    )
    (net (code "77") (name "unconnected-(U4A-ADC_INA4{slash}COMP2A{slash}AIO4-Pad19)") (class "Default")
      (node (ref "U4") (pin "19") (pinfunction "ADC_INA4/COMP2A/AIO4_19") (pintype "bidirectional"))
    )
    (net (code "78") (name "unconnected-(U4A-ADC_INA5-Pad18)") (class "Default")
      (node (ref "U4") (pin "18") (pinfunction "ADC_INA5_18") (pintype "input"))
    )
    (net (code "79") (name "unconnected-(U4A-ADC_INA6{slash}COMP3A{slash}AIO6-Pad17)") (class "Default")
      (node (ref "U4") (pin "17") (pinfunction "ADC_INA6/COMP3A/AIO6_17") (pintype "bidirectional"))
    )
    (net (code "80") (name "unconnected-(U4A-ADC_INB3-Pad31)") (class "Default")
      (node (ref "U4") (pin "31") (pinfunction "ADC_INB3_31") (pintype "input"))
    )
    (net (code "81") (name "unconnected-(U4A-ADC_INB4{slash}COMP2B{slash}AIO12-Pad32)") (class "Default")
      (node (ref "U4") (pin "32") (pinfunction "ADC_INB4/COMP2B/AIO12_32") (pintype "bidirectional"))
    )
    (net (code "82") (name "unconnected-(U4A-ADC_INB5-Pad33)") (class "Default")
      (node (ref "U4") (pin "33") (pinfunction "ADC_INB5_33") (pintype "input"))
    )
    (net (code "83") (name "unconnected-(U4A-ADC_INB6{slash}COMP3B{slash}AIO14-Pad34)") (class "Default")
      (node (ref "U4") (pin "34") (pinfunction "ADC_INB6/COMP3B/AIO14_34") (pintype "bidirectional"))
    )
    (net (code "84") (name "unconnected-(U4A-ADC_INB7-Pad35)") (class "Default")
      (node (ref "U4") (pin "35") (pinfunction "ADC_INB7_35") (pintype "input"))
    )
    (net (code "85") (name "unconnected-(U4A-TEST2-Pad45)") (class "Default")
      (node (ref "U4") (pin "45") (pinfunction "TEST2_45") (pintype "output"))
    )
    (net (code "86") (name "unconnected-(U4A-VREFHI-Pad24)") (class "Default")
      (node (ref "U4") (pin "24") (pinfunction "VREFHI_24") (pintype "input"))
    )
    (net (code "87") (name "unconnected-(U4A-X1-Pad60)") (class "Default")
      (node (ref "U4") (pin "60") (pinfunction "X1_60") (pintype "input"))
    )
    (net (code "88") (name "unconnected-(U4A-X2-Pad59)") (class "Default")
      (node (ref "U4") (pin "59") (pinfunction "X2_59") (pintype "output"))
    )
    (net (code "89") (name "unconnected-(U4B-GPIO6{slash}EPWM4A{slash}EPWMSYNCI{slash}EPWMSYNCO-Pad58)") (class "Default")
      (node (ref "U4") (pin "58") (pinfunction "GPIO6/EPWM4A/EPWMSYNCI/EPWMSYNCO_58") (pintype "bidirectional"))
    )
    (net (code "90") (name "unconnected-(U4B-GPIO7{slash}EPWM4B{slash}SCIRXDA{slash}ECAP2-Pad57)") (class "Default")
      (node (ref "U4") (pin "57") (pinfunction "GPIO7/EPWM4B/SCIRXDA/ECAP2_57") (pintype "bidirectional"))
    )
    (net (code "91") (name "unconnected-(U4B-GPIO8{slash}EPWM5A{slash}ADCSOCAO-Pad54)") (class "Default")
      (node (ref "U4") (pin "54") (pinfunction "GPIO8/EPWM5A/ADCSOCAO_54") (pintype "bidirectional"))
    )
    (net (code "92") (name "unconnected-(U4B-GPIO10{slash}EPWM6A{slash}ADCSOCBO-Pad74)") (class "Default")
      (node (ref "U4") (pin "74") (pinfunction "GPIO10/EPWM6A/ADCSOCBO_74") (pintype "bidirectional"))
    )
    (net (code "93") (name "unconnected-(U4B-GPIO11{slash}EPWM6B{slash}SCI_RXDB{slash}ECAP1-Pad73)") (class "Default")
      (node (ref "U4") (pin "73") (pinfunction "GPIO11/EPWM6B/SCI_RXDB/ECAP1_73") (pintype "bidirectional"))
    )
    (net (code "94") (name "unconnected-(U4B-GPIO12{slash}TZ1{slash}SCITXDA{slash}SPISIMOB-Pad44)") (class "Default")
      (node (ref "U4") (pin "44") (pinfunction "GPIO12/TZ1/SCITXDA/SPISIMOB_44") (pintype "bidirectional"))
    )
    (net (code "95") (name "unconnected-(U4B-GPIO13{slash}TZ2{slash}SPISOMIB-Pad95)") (class "Default")
      (node (ref "U4") (pin "95") (pinfunction "GPIO13/TZ2/SPISOMIB_95") (pintype "bidirectional"))
    )
    (net (code "96") (name "unconnected-(U4B-GPIO14{slash}TZ3{slash}SCITXDB{slash}SPICLKB-Pad96)") (class "Default")
      (node (ref "U4") (pin "96") (pinfunction "GPIO14/TZ3/SCITXDB/SPICLKB_96") (pintype "bidirectional"))
    )
    (net (code "97") (name "unconnected-(U4B-GPIO15{slash}ECAP2{slash}SCI_RXDB{slash}SPISTEB-Pad88)") (class "Default")
      (node (ref "U4") (pin "88") (pinfunction "GPIO15/ECAP2/SCI_RXDB/SPISTEB_88") (pintype "bidirectional"))
    )
    (net (code "98") (name "unconnected-(U4B-GPIO20{slash}EQEP1A{slash}MDXA{slash}COMP1OUT-Pad6)") (class "Default")
      (node (ref "U4") (pin "6") (pinfunction "GPIO20/EQEP1A/MDXA/COMP1OUT_6") (pintype "bidirectional"))
    )
    (net (code "99") (name "unconnected-(U4B-GPIO21{slash}EQEP1B{slash}MDRA{slash}COMP2OUT-Pad7)") (class "Default")
      (node (ref "U4") (pin "7") (pinfunction "GPIO21/EQEP1B/MDRA/COMP2OUT_7") (pintype "bidirectional"))
    )
    (net (code "100") (name "unconnected-(U4B-GPIO22{slash}EQEP1S{slash}MCLKXA{slash}SCITXDB-Pad98)") (class "Default")
      (node (ref "U4") (pin "98") (pinfunction "GPIO22/EQEP1S/MCLKXA/SCITXDB_98") (pintype "bidirectional"))
    )
    (net (code "101") (name "unconnected-(U4B-GPIO23{slash}EQEP1I{slash}MFSXA{slash}SCIRXDB-Pad2)") (class "Default")
      (node (ref "U4") (pin "2") (pinfunction "GPIO23/EQEP1I/MFSXA/SCIRXDB_2") (pintype "bidirectional"))
    )
    (net (code "102") (name "unconnected-(U4B-GPIO24{slash}ECAP1{slash}EQEP2A{slash}SPISIMOB-Pad97)") (class "Default")
      (node (ref "U4") (pin "97") (pinfunction "GPIO24/ECAP1/EQEP2A/SPISIMOB_97") (pintype "bidirectional"))
    )
    (net (code "103") (name "unconnected-(U4B-GPIO25{slash}ECAP2{slash}EQEP2B{slash}SPISOMIB-Pad39)") (class "Default")
      (node (ref "U4") (pin "39") (pinfunction "GPIO25/ECAP2/EQEP2B/SPISOMIB_39") (pintype "bidirectional"))
    )
    (net (code "104") (name "unconnected-(U4B-GPIO26{slash}ECAP3{slash}EQEP2I{slash}SPICLKB{slash}USB0DP-Pad78)") (class "Default")
      (node (ref "U4") (pin "78") (pinfunction "GPIO26/ECAP3/EQEP2I/SPICLKB/USB0DP_78") (pintype "bidirectional"))
    )
    (net (code "105") (name "unconnected-(U4B-GPIO27{slash}HRCAP2{slash}EQEP2S{slash}SPISTEB{slash}USB0DM-Pad77)") (class "Default")
      (node (ref "U4") (pin "77") (pinfunction "GPIO27/HRCAP2/EQEP2S/SPISTEB/USB0DM_77") (pintype "bidirectional"))
    )
    (net (code "106") (name "unconnected-(U4B-GPIO30{slash}CAN_RXA{slash}EQEP2I{slash}EPWM7A-Pad41)") (class "Default")
      (node (ref "U4") (pin "41") (pinfunction "GPIO30/CAN_RXA/EQEP2I/EPWM7A_41") (pintype "bidirectional"))
    )
    (net (code "107") (name "unconnected-(U4B-GPIO31{slash}CAN_TXA{slash}EQEP2S{slash}EPWM8A-Pad40)") (class "Default")
      (node (ref "U4") (pin "40") (pinfunction "GPIO31/CAN_TXA/EQEP2S/EPWM8A_40") (pintype "bidirectional"))
    )
    (net (code "108") (name "unconnected-(U4B-GPIO39-Pad66)") (class "Default")
      (node (ref "U4") (pin "66") (pinfunction "GPIO39_66") (pintype "bidirectional"))
    )
    (net (code "109") (name "unconnected-(U4B-GPIO40{slash}EPWM7A{slash}SCI_TXDB-Pad82)") (class "Default")
      (node (ref "U4") (pin "82") (pinfunction "GPIO40/EPWM7A/SCI_TXDB_82") (pintype "bidirectional"))
    )
    (net (code "110") (name "unconnected-(U4B-GPIO41{slash}EPWM7B{slash}SCI_RXDB-Pad76)") (class "Default")
      (node (ref "U4") (pin "76") (pinfunction "GPIO41/EPWM7B/SCI_RXDB_76") (pintype "bidirectional"))
    )
    (net (code "111") (name "unconnected-(U4B-GPIO42{slash}EPWM8A{slash}~{TZ1}{slash}COMP1OUT-Pad1)") (class "Default")
      (node (ref "U4") (pin "1") (pinfunction "GPIO42/EPWM8A/~{TZ1}/COMP1OUT_1") (pintype "bidirectional"))
    )
    (net (code "112") (name "unconnected-(U4B-GPIO43{slash}EPWM8B{slash}~{TZ2}{slash}COMP2OUT-Pad8)") (class "Default")
      (node (ref "U4") (pin "8") (pinfunction "GPIO43/EPWM8B/~{TZ2}/COMP2OUT_8") (pintype "bidirectional"))
    )
    (net (code "113") (name "unconnected-(U4B-GPIO44{slash}MFSRA{slash}SCIRXDB{slash}EPWM7B-Pad56)") (class "Default")
      (node (ref "U4") (pin "56") (pinfunction "GPIO44/MFSRA/SCIRXDB/EPWM7B_56") (pintype "bidirectional"))
    )
    (net (code "114") (name "unconnected-(U4B-GPIO52{slash}EQEP1S{slash}MCLKXA{slash}TZ3-Pad53)") (class "Default")
      (node (ref "U4") (pin "53") (pinfunction "GPIO52/EQEP1S/MCLKXA/TZ3_53") (pintype "bidirectional"))
    )
    (net (code "115") (name "unconnected-(U4B-GPIO53{slash}EQEP1I{slash}MFSXA-Pad65)") (class "Default")
      (node (ref "U4") (pin "65") (pinfunction "GPIO53/EQEP1I/MFSXA_65") (pintype "bidirectional"))
    )
    (net (code "116") (name "unconnected-(U4B-GPIO54{slash}SPISIMOA{slash}EQEP2A{slash}HRCAP1-Pad69)") (class "Default")
      (node (ref "U4") (pin "69") (pinfunction "GPIO54/SPISIMOA/EQEP2A/HRCAP1_69") (pintype "bidirectional"))
    )
    (net (code "117") (name "unconnected-(U4B-GPIO55{slash}SPISOMIA{slash}EQEP2B{slash}HRCAP2-Pad75)") (class "Default")
      (node (ref "U4") (pin "75") (pinfunction "GPIO55/SPISOMIA/EQEP2B/HRCAP2_75") (pintype "bidirectional"))
    )
    (net (code "118") (name "unconnected-(U4B-GPIO56{slash}SPICLKA{slash}EQEP2I{slash}HRCAP3-Pad85)") (class "Default")
      (node (ref "U4") (pin "85") (pinfunction "GPIO56/SPICLKA/EQEP2I/HRCAP3_85") (pintype "bidirectional"))
    )
    (net (code "119") (name "unconnected-(U4B-GPIO57{slash}SPISTEA{slash}EQEP2S{slash}HRCAP4-Pad89)") (class "Default")
      (node (ref "U4") (pin "89") (pinfunction "GPIO57/SPISTEA/EQEP2S/HRCAP4_89") (pintype "bidirectional"))
    )
    (net (code "120") (name "unconnected-(U4B-GPIO58{slash}MCLKRA{slash}SCI_TXDB{slash}EPWM7A-Pad94)") (class "Default")
      (node (ref "U4") (pin "94") (pinfunction "GPIO58/MCLKRA/SCI_TXDB/EPWM7A_94") (pintype "bidirectional"))
    )
  )
)
